# BOC_KB.net
KiCad netlist of a schematic drawn in Altium Designer
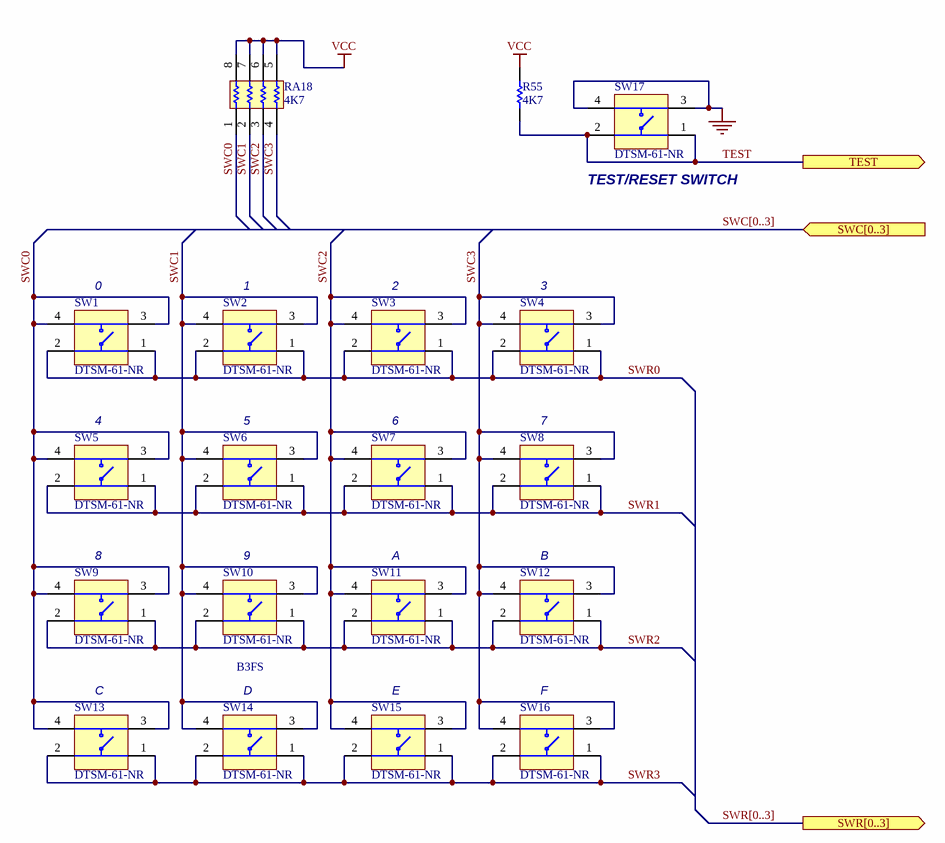
[diagram p0: BOC_KB.SchDoc]

(export (version "E")
  (design (tool "Eeschema 10.0.6"))
  (components
    (comp (ref "R55")
      (value "4K7")
      (footprint "Altium Nanoboard Project:CC2012-0805")
      (description "Resistor")
      (libsource (lib "Altium Nanoboard Project") (part "RES"))
    )
    (comp (ref "RA18")
      (value "4K7")
      (footprint "Altium Nanoboard Project:MNR34")
      (description "3216x4 Resistor Array")
      (libsource (lib "Altium Nanoboard Project") (part "MNR34"))
    )
    (comp (ref "SW1")
      (value "DTSM-61-NR")
      (footprint "Altium Nanoboard Project:B3FS_SWITCH")
      (description "SPNA SMD Keyboard Switch")
      (libsource (lib "Altium Nanoboard Project") (part "B3FS"))
    )
    (comp (ref "SW2")
      (value "DTSM-61-NR")
      (footprint "Altium Nanoboard Project:B3FS_SWITCH")
      (description "SPNA SMD Keyboard Switch")
      (libsource (lib "Altium Nanoboard Project") (part "B3FS"))
    )
    (comp (ref "SW3")
      (value "DTSM-61-NR")
      (footprint "Altium Nanoboard Project:B3FS_SWITCH")
      (description "SPNA SMD Keyboard Switch")
      (libsource (lib "Altium Nanoboard Project") (part "B3FS"))
    )
    (comp (ref "SW4")
      (value "DTSM-61-NR")
      (footprint "Altium Nanoboard Project:B3FS_SWITCH")
      (description "SPNA SMD Keyboard Switch")
      (libsource (lib "Altium Nanoboard Project") (part "B3FS"))
    )
    (comp (ref "SW5")
      (value "DTSM-61-NR")
      (footprint "Altium Nanoboard Project:B3FS_SWITCH")
      (description "SPNA SMD Keyboard Switch")
      (libsource (lib "Altium Nanoboard Project") (part "B3FS"))
    )
    (comp (ref "SW6")
      (value "DTSM-61-NR")
      (footprint "Altium Nanoboard Project:B3FS_SWITCH")
      (description "SPNA SMD Keyboard Switch")
      (libsource (lib "Altium Nanoboard Project") (part "B3FS"))
    )
    (comp (ref "SW7")
      (value "DTSM-61-NR")
      (footprint "Altium Nanoboard Project:B3FS_SWITCH")
      (description "SPNA SMD Keyboard Switch")
      (libsource (lib "Altium Nanoboard Project") (part "B3FS"))
    )
    (comp (ref "SW8")
      (value "DTSM-61-NR")
      (footprint "Altium Nanoboard Project:B3FS_SWITCH")
      (description "SPNA SMD Keyboard Switch")
      (libsource (lib "Altium Nanoboard Project") (part "B3FS"))
    )
    (comp (ref "SW9")
      (value "DTSM-61-NR")
      (footprint "Altium Nanoboard Project:B3FS_SWITCH")
      (description "SPNA SMD Keyboard Switch")
      (libsource (lib "Altium Nanoboard Project") (part "B3FS"))
    )
    (comp (ref "SW10")
      (value "DTSM-61-NR")
      (footprint "Altium Nanoboard Project:B3FS_SWITCH")
      (description "SPNA SMD Keyboard Switch")
      (fields (field (name "COMMENT_1") "B3FS"))
      (libsource (lib "Altium Nanoboard Project") (part "B3FS"))
    )
    (comp (ref "SW11")
      (value "DTSM-61-NR")
      (footprint "Altium Nanoboard Project:B3FS_SWITCH")
      (description "SPNA SMD Keyboard Switch")
      (libsource (lib "Altium Nanoboard Project") (part "B3FS"))
    )
    (comp (ref "SW12")
      (value "DTSM-61-NR")
      (footprint "Altium Nanoboard Project:B3FS_SWITCH")
      (description "SPNA SMD Keyboard Switch")
      (libsource (lib "Altium Nanoboard Project") (part "B3FS"))
    )
    (comp (ref "SW13")
      (value "DTSM-61-NR")
      (footprint "Altium Nanoboard Project:B3FS_SWITCH")
      (description "SPNA SMD Keyboard Switch")
      (libsource (lib "Altium Nanoboard Project") (part "B3FS"))
    )
    (comp (ref "SW14")
      (value "DTSM-61-NR")
      (footprint "Altium Nanoboard Project:B3FS_SWITCH")
      (description "SPNA SMD Keyboard Switch")
      (libsource (lib "Altium Nanoboard Project") (part "B3FS"))
    )
    (comp (ref "SW15")
      (value "DTSM-61-NR")
      (footprint "Altium Nanoboard Project:B3FS_SWITCH")
      (description "SPNA SMD Keyboard Switch")
      (libsource (lib "Altium Nanoboard Project") (part "B3FS"))
    )
    (comp (ref "SW16")
      (value "DTSM-61-NR")
      (footprint "Altium Nanoboard Project:B3FS_SWITCH")
      (description "SPNA SMD Keyboard Switch")
      (libsource (lib "Altium Nanoboard Project") (part "B3FS"))
    )
    (comp (ref "SW17")
      (value "DTSM-61-NR")
      (footprint "Altium Nanoboard Project:B3FS_SWITCH")
      (description "SPNA SMD Keyboard Switch")
      (libsource (lib "Altium Nanoboard Project") (part "B3FS"))
    )
  )
  (nets
    (net (code "1") (name "/SWC0") (class "Default")
      (node (ref "RA18") (pin "1") (pintype "passive"))
      (node (ref "SW1") (pin "3") (pinfunction "3_3") (pintype "passive"))
      (node (ref "SW1") (pin "4") (pinfunction "4_4") (pintype "passive"))
      (node (ref "SW13") (pin "3") (pinfunction "3_3") (pintype "passive"))
      (node (ref "SW13") (pin "4") (pinfunction "4_4") (pintype "passive"))
      (node (ref "SW5") (pin "3") (pinfunction "3_3") (pintype "passive"))
      (node (ref "SW5") (pin "4") (pinfunction "4_4") (pintype "passive"))
      (node (ref "SW9") (pin "3") (pinfunction "3_3") (pintype "passive"))
      (node (ref "SW9") (pin "4") (pinfunction "4_4") (pintype "passive"))
    )
    (net (code "2") (name "/SWC1") (class "Default")
      (node (ref "RA18") (pin "2") (pintype "passive"))
      (node (ref "SW10") (pin "3") (pinfunction "3_3") (pintype "passive"))
      (node (ref "SW10") (pin "4") (pinfunction "4_4") (pintype "passive"))
      (node (ref "SW14") (pin "3") (pinfunction "3_3") (pintype "passive"))
      (node (ref "SW14") (pin "4") (pinfunction "4_4") (pintype "passive"))
      (node (ref "SW2") (pin "3") (pinfunction "3_3") (pintype "passive"))
      (node (ref "SW2") (pin "4") (pinfunction "4_4") (pintype "passive"))
      (node (ref "SW6") (pin "3") (pinfunction "3_3") (pintype "passive"))
      (node (ref "SW6") (pin "4") (pinfunction "4_4") (pintype "passive"))
    )
    (net (code "3") (name "/SWC2") (class "Default")
      (node (ref "RA18") (pin "3") (pintype "passive"))
      (node (ref "SW11") (pin "3") (pinfunction "3_3") (pintype "passive"))
      (node (ref "SW11") (pin "4") (pinfunction "4_4") (pintype "passive"))
      (node (ref "SW15") (pin "3") (pinfunction "3_3") (pintype "passive"))
      (node (ref "SW15") (pin "4") (pinfunction "4_4") (pintype "passive"))
      (node (ref "SW3") (pin "3") (pinfunction "3_3") (pintype "passive"))
      (node (ref "SW3") (pin "4") (pinfunction "4_4") (pintype "passive"))
      (node (ref "SW7") (pin "3") (pinfunction "3_3") (pintype "passive"))
      (node (ref "SW7") (pin "4") (pinfunction "4_4") (pintype "passive"))
    )
    (net (code "4") (name "/SWC3") (class "Default")
      (node (ref "RA18") (pin "4") (pintype "passive"))
      (node (ref "SW12") (pin "3") (pinfunction "3_3") (pintype "passive"))
      (node (ref "SW12") (pin "4") (pinfunction "4_4") (pintype "passive"))
      (node (ref "SW16") (pin "3") (pinfunction "3_3") (pintype "passive"))
      (node (ref "SW16") (pin "4") (pinfunction "4_4") (pintype "passive"))
      (node (ref "SW4") (pin "3") (pinfunction "3_3") (pintype "passive"))
      (node (ref "SW4") (pin "4") (pinfunction "4_4") (pintype "passive"))
      (node (ref "SW8") (pin "3") (pinfunction "3_3") (pintype "passive"))
      (node (ref "SW8") (pin "4") (pinfunction "4_4") (pintype "passive"))
    )
    (net (code "6") (name "/SWR0") (class "Default")
      (node (ref "SW1") (pin "1") (pinfunction "1_1") (pintype "passive"))
      (node (ref "SW1") (pin "2") (pinfunction "2_2") (pintype "passive"))
      (node (ref "SW2") (pin "1") (pinfunction "1_1") (pintype "passive"))
      (node (ref "SW2") (pin "2") (pinfunction "2_2") (pintype "passive"))
      (node (ref "SW3") (pin "1") (pinfunction "1_1") (pintype "passive"))
      (node (ref "SW3") (pin "2") (pinfunction "2_2") (pintype "passive"))
      (node (ref "SW4") (pin "1") (pinfunction "1_1") (pintype "passive"))
      (node (ref "SW4") (pin "2") (pinfunction "2_2") (pintype "passive"))
    )
    (net (code "7") (name "/SWR1") (class "Default")
      (node (ref "SW5") (pin "1") (pinfunction "1_1") (pintype "passive"))
      (node (ref "SW5") (pin "2") (pinfunction "2_2") (pintype "passive"))
      (node (ref "SW6") (pin "1") (pinfunction "1_1") (pintype "passive"))
      (node (ref "SW6") (pin "2") (pinfunction "2_2") (pintype "passive"))
      (node (ref "SW7") (pin "1") (pinfunction "1_1") (pintype "passive"))
      (node (ref "SW7") (pin "2") (pinfunction "2_2") (pintype "passive"))
      (node (ref "SW8") (pin "1") (pinfunction "1_1") (pintype "passive"))
      (node (ref "SW8") (pin "2") (pinfunction "2_2") (pintype "passive"))
    )
    (net (code "8") (name "/SWR2") (class "Default")
      (node (ref "SW10") (pin "1") (pinfunction "1_1") (pintype "passive"))
      (node (ref "SW10") (pin "2") (pinfunction "2_2") (pintype "passive"))
      (node (ref "SW11") (pin "1") (pinfunction "1_1") (pintype "passive"))
      (node (ref "SW11") (pin "2") (pinfunction "2_2") (pintype "passive"))
      (node (ref "SW12") (pin "1") (pinfunction "1_1") (pintype "passive"))
      (node (ref "SW12") (pin "2") (pinfunction "2_2") (pintype "passive"))
      (node (ref "SW9") (pin "1") (pinfunction "1_1") (pintype "passive"))
      (node (ref "SW9") (pin "2") (pinfunction "2_2") (pintype "passive"))
    )
    (net (code "9") (name "/SWR3") (class "Default")
      (node (ref "SW13") (pin "1") (pinfunction "1_1") (pintype "passive"))
      (node (ref "SW13") (pin "2") (pinfunction "2_2") (pintype "passive"))
      (node (ref "SW14") (pin "1") (pinfunction "1_1") (pintype "passive"))
      (node (ref "SW14") (pin "2") (pinfunction "2_2") (pintype "passive"))
      (node (ref "SW15") (pin "1") (pinfunction "1_1") (pintype "passive"))
      (node (ref "SW15") (pin "2") (pinfunction "2_2") (pintype "passive"))
      (node (ref "SW16") (pin "1") (pinfunction "1_1") (pintype "passive"))
      (node (ref "SW16") (pin "2") (pinfunction "2_2") (pintype "passive"))
    )
    (net (code "11") (name "/TEST") (class "Default")
      (node (ref "R55") (pin "2") (pinfunction "2_2") (pintype "passive"))
      (node (ref "SW17") (pin "1") (pinfunction "1_1") (pintype "passive"))
      (node (ref "SW17") (pin "2") (pinfunction "2_2") (pintype "passive"))
    )
    (net (code "12") (name "GND") (class "Default")
      (node (ref "SW17") (pin "3") (pinfunction "3_3") (pintype "passive"))
      (node (ref "SW17") (pin "4") (pinfunction "4_4") (pintype "passive"))
    )
    (net (code "13") (name "VCC") (class "Default")
      (node (ref "R55") (pin "1") (pinfunction "1_1") (pintype "passive"))
      (node (ref "RA18") (pin "5") (pintype "passive"))
      (node (ref "RA18") (pin "6") (pintype "passive"))
      (node (ref "RA18") (pin "7") (pintype "passive"))
      (node (ref "RA18") (pin "8") (pintype "passive"))
    )
  )
)
